# GPIO_OUT.net
KiCad netlist of a schematic drawn in Altium Designer
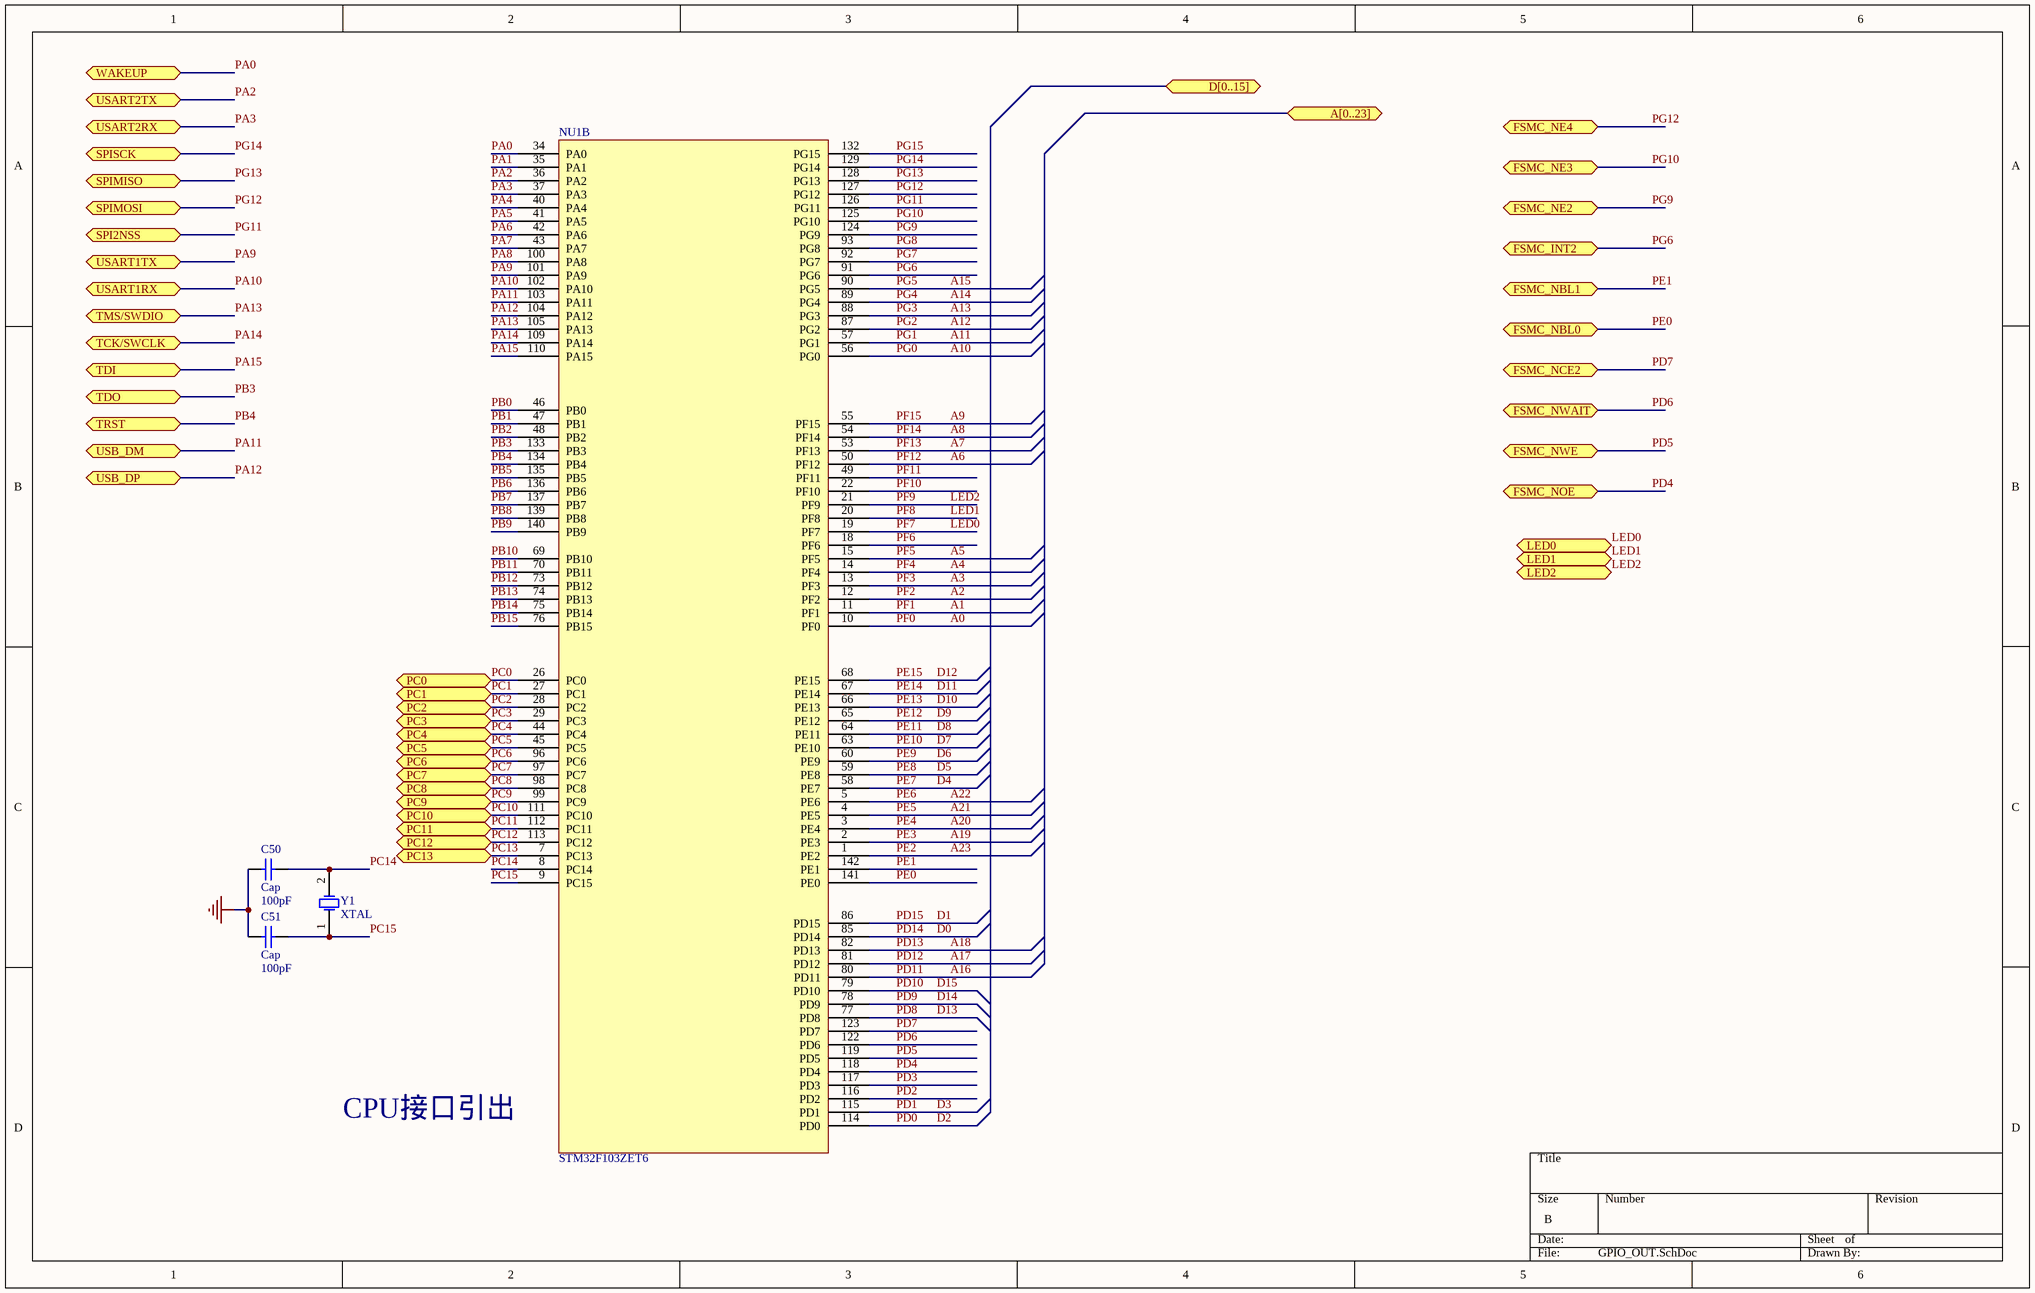
[diagram p0: GPIO_OUT.SchDoc]

(export (version "E")
  (design (tool "Eeschema 10.0.6"))
  (components
    (comp (ref "C50")
      (value "Cap")
      (footprint "0805")
      (description "Capacitor")
      (fields (field (name "ALTIUM_VALUE") "100pF") (field (name "PUBLISHER") "Altium Limited"))
      (libsource (lib "Miscellaneous Devices") (part "Cap"))
    )
    (comp (ref "C51")
      (value "Cap")
      (footprint "0805")
      (description "Capacitor")
      (fields (field (name "ALTIUM_VALUE") "100pF") (field (name "PUBLISHER") "Altium Limited"))
      (libsource (lib "Miscellaneous Devices") (part "Cap"))
    )
    (comp (ref "NU1") (value "STM32F103ZET6") (libsource (lib "Schlib1") (part "STM32F103ZET6")))
    (comp (ref "Y1")
      (value "XTAL")
      (footprint "XTAL-1")
      (description "Crystal Oscillator")
      (fields (field (name "PUBLISHER") "Altium Limited"))
      (libsource (lib "Miscellaneous Devices") (part "XTAL"))
    )
  )
  (nets
    (net (code "1") (name "/A0") (class "Default")
      (node (ref "NU1") (pin "10") (pinfunction "PF0_10") (pintype "passive"))
    )
    (net (code "2") (name "/A1") (class "Default")
      (node (ref "NU1") (pin "11") (pinfunction "PF1_11") (pintype "passive"))
    )
    (net (code "3") (name "/A2") (class "Default")
      (node (ref "NU1") (pin "12") (pinfunction "PF2_12") (pintype "passive"))
    )
    (net (code "4") (name "/A3") (class "Default")
      (node (ref "NU1") (pin "13") (pinfunction "PF3_13") (pintype "passive"))
    )
    (net (code "5") (name "/A4") (class "Default")
      (node (ref "NU1") (pin "14") (pinfunction "PF4_14") (pintype "passive"))
    )
    (net (code "6") (name "/A5") (class "Default")
      (node (ref "NU1") (pin "15") (pinfunction "PF5_15") (pintype "passive"))
    )
    (net (code "7") (name "/A6") (class "Default")
      (node (ref "NU1") (pin "50") (pinfunction "PF12_50") (pintype "passive"))
    )
    (net (code "8") (name "/A7") (class "Default")
      (node (ref "NU1") (pin "53") (pinfunction "PF13_53") (pintype "passive"))
    )
    (net (code "9") (name "/A8") (class "Default")
      (node (ref "NU1") (pin "54") (pinfunction "PF14_54") (pintype "passive"))
    )
    (net (code "10") (name "/A9") (class "Default")
      (node (ref "NU1") (pin "55") (pinfunction "PF15_55") (pintype "passive"))
    )
    (net (code "11") (name "/A10") (class "Default")
      (node (ref "NU1") (pin "56") (pinfunction "PG0_56") (pintype "passive"))
    )
    (net (code "12") (name "/A11") (class "Default")
      (node (ref "NU1") (pin "57") (pinfunction "PG1_57") (pintype "passive"))
    )
    (net (code "13") (name "/A12") (class "Default")
      (node (ref "NU1") (pin "87") (pinfunction "PG2_87") (pintype "passive"))
    )
    (net (code "14") (name "/A13") (class "Default")
      (node (ref "NU1") (pin "88") (pinfunction "PG3_88") (pintype "passive"))
    )
    (net (code "15") (name "/A14") (class "Default")
      (node (ref "NU1") (pin "89") (pinfunction "PG4_89") (pintype "passive"))
    )
    (net (code "16") (name "/A15") (class "Default")
      (node (ref "NU1") (pin "90") (pinfunction "PG5_90") (pintype "passive"))
    )
    (net (code "17") (name "/A16") (class "Default")
      (node (ref "NU1") (pin "80") (pinfunction "PD11_80") (pintype "passive"))
    )
    (net (code "18") (name "/A17") (class "Default")
      (node (ref "NU1") (pin "81") (pinfunction "PD12_81") (pintype "passive"))
    )
    (net (code "19") (name "/A18") (class "Default")
      (node (ref "NU1") (pin "82") (pinfunction "PD13_82") (pintype "passive"))
    )
    (net (code "20") (name "/A19") (class "Default")
      (node (ref "NU1") (pin "2") (pinfunction "PE3_2") (pintype "passive"))
    )
    (net (code "21") (name "/A20") (class "Default")
      (node (ref "NU1") (pin "3") (pinfunction "PE4_3") (pintype "passive"))
    )
    (net (code "22") (name "/A21") (class "Default")
      (node (ref "NU1") (pin "4") (pinfunction "PE5_4") (pintype "passive"))
    )
    (net (code "23") (name "/A22") (class "Default")
      (node (ref "NU1") (pin "5") (pinfunction "PE6_5") (pintype "passive"))
    )
    (net (code "24") (name "/A23") (class "Default")
      (node (ref "NU1") (pin "1") (pinfunction "PE2_1") (pintype "passive"))
    )
    (net (code "26") (name "/D0") (class "Default")
      (node (ref "NU1") (pin "85") (pinfunction "PD14_85") (pintype "passive"))
    )
    (net (code "27") (name "/D1") (class "Default")
      (node (ref "NU1") (pin "86") (pinfunction "PD15_86") (pintype "passive"))
    )
    (net (code "28") (name "/D2") (class "Default")
      (node (ref "NU1") (pin "114") (pinfunction "PD0_114") (pintype "passive"))
    )
    (net (code "29") (name "/D3") (class "Default")
      (node (ref "NU1") (pin "115") (pinfunction "PD1_115") (pintype "passive"))
    )
    (net (code "30") (name "/D4") (class "Default")
      (node (ref "NU1") (pin "58") (pinfunction "PE7_58") (pintype "passive"))
    )
    (net (code "31") (name "/D5") (class "Default")
      (node (ref "NU1") (pin "59") (pinfunction "PE8_59") (pintype "passive"))
    )
    (net (code "32") (name "/D6") (class "Default")
      (node (ref "NU1") (pin "60") (pinfunction "PE9_60") (pintype "passive"))
    )
    (net (code "33") (name "/D7") (class "Default")
      (node (ref "NU1") (pin "63") (pinfunction "PE10_63") (pintype "passive"))
    )
    (net (code "34") (name "/D8") (class "Default")
      (node (ref "NU1") (pin "64") (pinfunction "PE11_64") (pintype "passive"))
    )
    (net (code "35") (name "/D9") (class "Default")
      (node (ref "NU1") (pin "65") (pinfunction "PE12_65") (pintype "passive"))
    )
    (net (code "36") (name "/D10") (class "Default")
      (node (ref "NU1") (pin "66") (pinfunction "PE13_66") (pintype "passive"))
    )
    (net (code "37") (name "/D11") (class "Default")
      (node (ref "NU1") (pin "67") (pinfunction "PE14_67") (pintype "passive"))
    )
    (net (code "38") (name "/D12") (class "Default")
      (node (ref "NU1") (pin "68") (pinfunction "PE15_68") (pintype "passive"))
    )
    (net (code "39") (name "/D13") (class "Default")
      (node (ref "NU1") (pin "77") (pinfunction "PD8_77") (pintype "passive"))
    )
    (net (code "40") (name "/D14") (class "Default")
      (node (ref "NU1") (pin "78") (pinfunction "PD9_78") (pintype "passive"))
    )
    (net (code "41") (name "/D15") (class "Default")
      (node (ref "NU1") (pin "79") (pinfunction "PD10_79") (pintype "passive"))
    )
    (net (code "43") (name "/LED0") (class "Default")
      (node (ref "NU1") (pin "19") (pinfunction "PF7_19") (pintype "passive"))
    )
    (net (code "44") (name "/LED1") (class "Default")
      (node (ref "NU1") (pin "20") (pinfunction "PF8_20") (pintype "passive"))
    )
    (net (code "45") (name "/LED2") (class "Default")
      (node (ref "NU1") (pin "21") (pinfunction "PF9_21") (pintype "passive"))
    )
    (net (code "46") (name "/PA0") (class "Default")
      (node (ref "NU1") (pin "34") (pinfunction "PA0_34") (pintype "passive"))
    )
    (net (code "47") (name "/PA1") (class "Default")
      (node (ref "NU1") (pin "35") (pinfunction "PA1_35") (pintype "passive"))
    )
    (net (code "48") (name "/PA2") (class "Default")
      (node (ref "NU1") (pin "36") (pinfunction "PA2_36") (pintype "passive"))
    )
    (net (code "49") (name "/PA3") (class "Default")
      (node (ref "NU1") (pin "37") (pinfunction "PA3_37") (pintype "passive"))
    )
    (net (code "50") (name "/PA4") (class "Default")
      (node (ref "NU1") (pin "40") (pinfunction "PA4_40") (pintype "passive"))
    )
    (net (code "51") (name "/PA5") (class "Default")
      (node (ref "NU1") (pin "41") (pinfunction "PA5_41") (pintype "passive"))
    )
    (net (code "52") (name "/PA6") (class "Default")
      (node (ref "NU1") (pin "42") (pinfunction "PA6_42") (pintype "passive"))
    )
    (net (code "53") (name "/PA7") (class "Default")
      (node (ref "NU1") (pin "43") (pinfunction "PA7_43") (pintype "passive"))
    )
    (net (code "54") (name "/PA8") (class "Default")
      (node (ref "NU1") (pin "100") (pinfunction "PA8_100") (pintype "passive"))
    )
    (net (code "55") (name "/PA9") (class "Default")
      (node (ref "NU1") (pin "101") (pinfunction "PA9_101") (pintype "passive"))
    )
    (net (code "56") (name "/PA10") (class "Default")
      (node (ref "NU1") (pin "102") (pinfunction "PA10_102") (pintype "passive"))
    )
    (net (code "57") (name "/PA11") (class "Default")
      (node (ref "NU1") (pin "103") (pinfunction "PA11_103") (pintype "passive"))
    )
    (net (code "58") (name "/PA12") (class "Default")
      (node (ref "NU1") (pin "104") (pinfunction "PA12_104") (pintype "passive"))
    )
    (net (code "59") (name "/PA13") (class "Default")
      (node (ref "NU1") (pin "105") (pinfunction "PA13_105") (pintype "passive"))
    )
    (net (code "60") (name "/PA14") (class "Default")
      (node (ref "NU1") (pin "109") (pinfunction "PA14_109") (pintype "passive"))
    )
    (net (code "61") (name "/PA15") (class "Default")
      (node (ref "NU1") (pin "110") (pinfunction "PA15_110") (pintype "passive"))
    )
    (net (code "62") (name "/PB0") (class "Default")
      (node (ref "NU1") (pin "46") (pinfunction "PB0_46") (pintype "passive"))
    )
    (net (code "63") (name "/PB1") (class "Default")
      (node (ref "NU1") (pin "47") (pinfunction "PB1_47") (pintype "passive"))
    )
    (net (code "64") (name "/PB2") (class "Default")
      (node (ref "NU1") (pin "48") (pinfunction "PB2_48") (pintype "passive"))
    )
    (net (code "65") (name "/PB3") (class "Default")
      (node (ref "NU1") (pin "133") (pinfunction "PB3_133") (pintype "passive"))
    )
    (net (code "66") (name "/PB4") (class "Default")
      (node (ref "NU1") (pin "134") (pinfunction "PB4_134") (pintype "passive"))
    )
    (net (code "67") (name "/PB5") (class "Default")
      (node (ref "NU1") (pin "135") (pinfunction "PB5_135") (pintype "passive"))
    )
    (net (code "68") (name "/PB6") (class "Default")
      (node (ref "NU1") (pin "136") (pinfunction "PB6_136") (pintype "passive"))
    )
    (net (code "69") (name "/PB7") (class "Default")
      (node (ref "NU1") (pin "137") (pinfunction "PB7_137") (pintype "passive"))
    )
    (net (code "70") (name "/PB8") (class "Default")
      (node (ref "NU1") (pin "139") (pinfunction "PB8_139") (pintype "passive"))
    )
    (net (code "71") (name "/PB9") (class "Default")
      (node (ref "NU1") (pin "140") (pinfunction "PB9_140") (pintype "passive"))
    )
    (net (code "72") (name "/PB10") (class "Default")
      (node (ref "NU1") (pin "69") (pinfunction "PB10_69") (pintype "passive"))
    )
    (net (code "73") (name "/PB11") (class "Default")
      (node (ref "NU1") (pin "70") (pinfunction "PB11_70") (pintype "passive"))
    )
    (net (code "74") (name "/PB12") (class "Default")
      (node (ref "NU1") (pin "73") (pinfunction "PB12_73") (pintype "passive"))
    )
    (net (code "75") (name "/PB13") (class "Default")
      (node (ref "NU1") (pin "74") (pinfunction "PB13_74") (pintype "passive"))
    )
    (net (code "76") (name "/PB14") (class "Default")
      (node (ref "NU1") (pin "75") (pinfunction "PB14_75") (pintype "passive"))
    )
    (net (code "77") (name "/PB15") (class "Default")
      (node (ref "NU1") (pin "76") (pinfunction "PB15_76") (pintype "passive"))
    )
    (net (code "78") (name "/PC0") (class "Default")
      (node (ref "NU1") (pin "26") (pinfunction "PC0_26") (pintype "passive"))
    )
    (net (code "79") (name "/PC1") (class "Default")
      (node (ref "NU1") (pin "27") (pinfunction "PC1_27") (pintype "passive"))
    )
    (net (code "80") (name "/PC2") (class "Default")
      (node (ref "NU1") (pin "28") (pinfunction "PC2_28") (pintype "passive"))
    )
    (net (code "81") (name "/PC3") (class "Default")
      (node (ref "NU1") (pin "29") (pinfunction "PC3_29") (pintype "passive"))
    )
    (net (code "82") (name "/PC4") (class "Default")
      (node (ref "NU1") (pin "44") (pinfunction "PC4_44") (pintype "passive"))
    )
    (net (code "83") (name "/PC5") (class "Default")
      (node (ref "NU1") (pin "45") (pinfunction "PC5_45") (pintype "passive"))
    )
    (net (code "84") (name "/PC6") (class "Default")
      (node (ref "NU1") (pin "96") (pinfunction "PC6_96") (pintype "passive"))
    )
    (net (code "85") (name "/PC7") (class "Default")
      (node (ref "NU1") (pin "97") (pinfunction "PC7_97") (pintype "passive"))
    )
    (net (code "86") (name "/PC8") (class "Default")
      (node (ref "NU1") (pin "98") (pinfunction "PC8_98") (pintype "passive"))
    )
    (net (code "87") (name "/PC9") (class "Default")
      (node (ref "NU1") (pin "99") (pinfunction "PC9_99") (pintype "passive"))
    )
    (net (code "88") (name "/PC10") (class "Default")
      (node (ref "NU1") (pin "111") (pinfunction "PC10_111") (pintype "passive"))
    )
    (net (code "89") (name "/PC11") (class "Default")
      (node (ref "NU1") (pin "112") (pinfunction "PC11_112") (pintype "passive"))
    )
    (net (code "90") (name "/PC12") (class "Default")
      (node (ref "NU1") (pin "113") (pinfunction "PC12_113") (pintype "passive"))
    )
    (net (code "91") (name "/PC13") (class "Default")
      (node (ref "NU1") (pin "7") (pinfunction "PC13_7") (pintype "passive"))
    )
    (net (code "92") (name "/PC14") (class "Default")
      (node (ref "C50") (pin "2") (pinfunction "2_2") (pintype "passive"))
      (node (ref "NU1") (pin "8") (pinfunction "PC14_8") (pintype "passive"))
      (node (ref "Y1") (pin "2") (pinfunction "OSC2_2") (pintype "passive"))
    )
    (net (code "93") (name "/PC15") (class "Default")
      (node (ref "C51") (pin "2") (pinfunction "2_2") (pintype "passive"))
      (node (ref "NU1") (pin "9") (pinfunction "PC15_9") (pintype "passive"))
      (node (ref "Y1") (pin "1") (pinfunction "OSC1_1") (pintype "passive"))
    )
    (net (code "94") (name "/PD2") (class "Default")
      (node (ref "NU1") (pin "116") (pinfunction "PD2_116") (pintype "passive"))
    )
    (net (code "95") (name "/PD3") (class "Default")
      (node (ref "NU1") (pin "117") (pinfunction "PD3_117") (pintype "passive"))
    )
    (net (code "96") (name "/PD4") (class "Default")
      (node (ref "NU1") (pin "118") (pinfunction "PD4_118") (pintype "passive"))
    )
    (net (code "97") (name "/PD5") (class "Default")
      (node (ref "NU1") (pin "119") (pinfunction "PD5_119") (pintype "passive"))
    )
    (net (code "98") (name "/PD6") (class "Default")
      (node (ref "NU1") (pin "122") (pinfunction "PD6_122") (pintype "passive"))
    )
    (net (code "99") (name "/PD7") (class "Default")
      (node (ref "NU1") (pin "123") (pinfunction "PD7_123") (pintype "passive"))
    )
    (net (code "100") (name "/PE0") (class "Default")
      (node (ref "NU1") (pin "141") (pinfunction "PE0_141") (pintype "passive"))
    )
    (net (code "101") (name "/PE1") (class "Default")
      (node (ref "NU1") (pin "142") (pinfunction "PE1_142") (pintype "passive"))
    )
    (net (code "102") (name "/PF6") (class "Default")
      (node (ref "NU1") (pin "18") (pinfunction "PF6_18") (pintype "passive"))
    )
    (net (code "103") (name "/PF10") (class "Default")
      (node (ref "NU1") (pin "22") (pinfunction "PF10_22") (pintype "passive"))
    )
    (net (code "104") (name "/PF11") (class "Default")
      (node (ref "NU1") (pin "49") (pinfunction "PF11_49") (pintype "passive"))
    )
    (net (code "105") (name "/PG6") (class "Default")
      (node (ref "NU1") (pin "91") (pinfunction "PG6_91") (pintype "passive"))
    )
    (net (code "106") (name "/PG7") (class "Default")
      (node (ref "NU1") (pin "92") (pinfunction "PG7_92") (pintype "passive"))
    )
    (net (code "107") (name "/PG8") (class "Default")
      (node (ref "NU1") (pin "93") (pinfunction "PG8_93") (pintype "passive"))
    )
    (net (code "108") (name "/PG9") (class "Default")
      (node (ref "NU1") (pin "124") (pinfunction "PG9_124") (pintype "passive"))
    )
    (net (code "109") (name "/PG10") (class "Default")
      (node (ref "NU1") (pin "125") (pinfunction "PG10_125") (pintype "passive"))
    )
    (net (code "110") (name "/PG11") (class "Default")
      (node (ref "NU1") (pin "126") (pinfunction "PG11_126") (pintype "passive"))
    )
    (net (code "111") (name "/PG12") (class "Default")
      (node (ref "NU1") (pin "127") (pinfunction "PG12_127") (pintype "passive"))
    )
    (net (code "112") (name "/PG13") (class "Default")
      (node (ref "NU1") (pin "128") (pinfunction "PG13_128") (pintype "passive"))
    )
    (net (code "113") (name "/PG14") (class "Default")
      (node (ref "NU1") (pin "129") (pinfunction "PG14_129") (pintype "passive"))
    )
    (net (code "114") (name "/PG15") (class "Default")
      (node (ref "NU1") (pin "132") (pinfunction "PG15_132") (pintype "passive"))
    )
    (net (code "115") (name "GND") (class "Default")
      (node (ref "C50") (pin "1") (pinfunction "1_1") (pintype "passive"))
      (node (ref "C51") (pin "1") (pinfunction "1_1") (pintype "passive"))
    )
  )
)
